# PHAS-AmpController.net
KiCad netlist of a schematic drawn in EAGLE
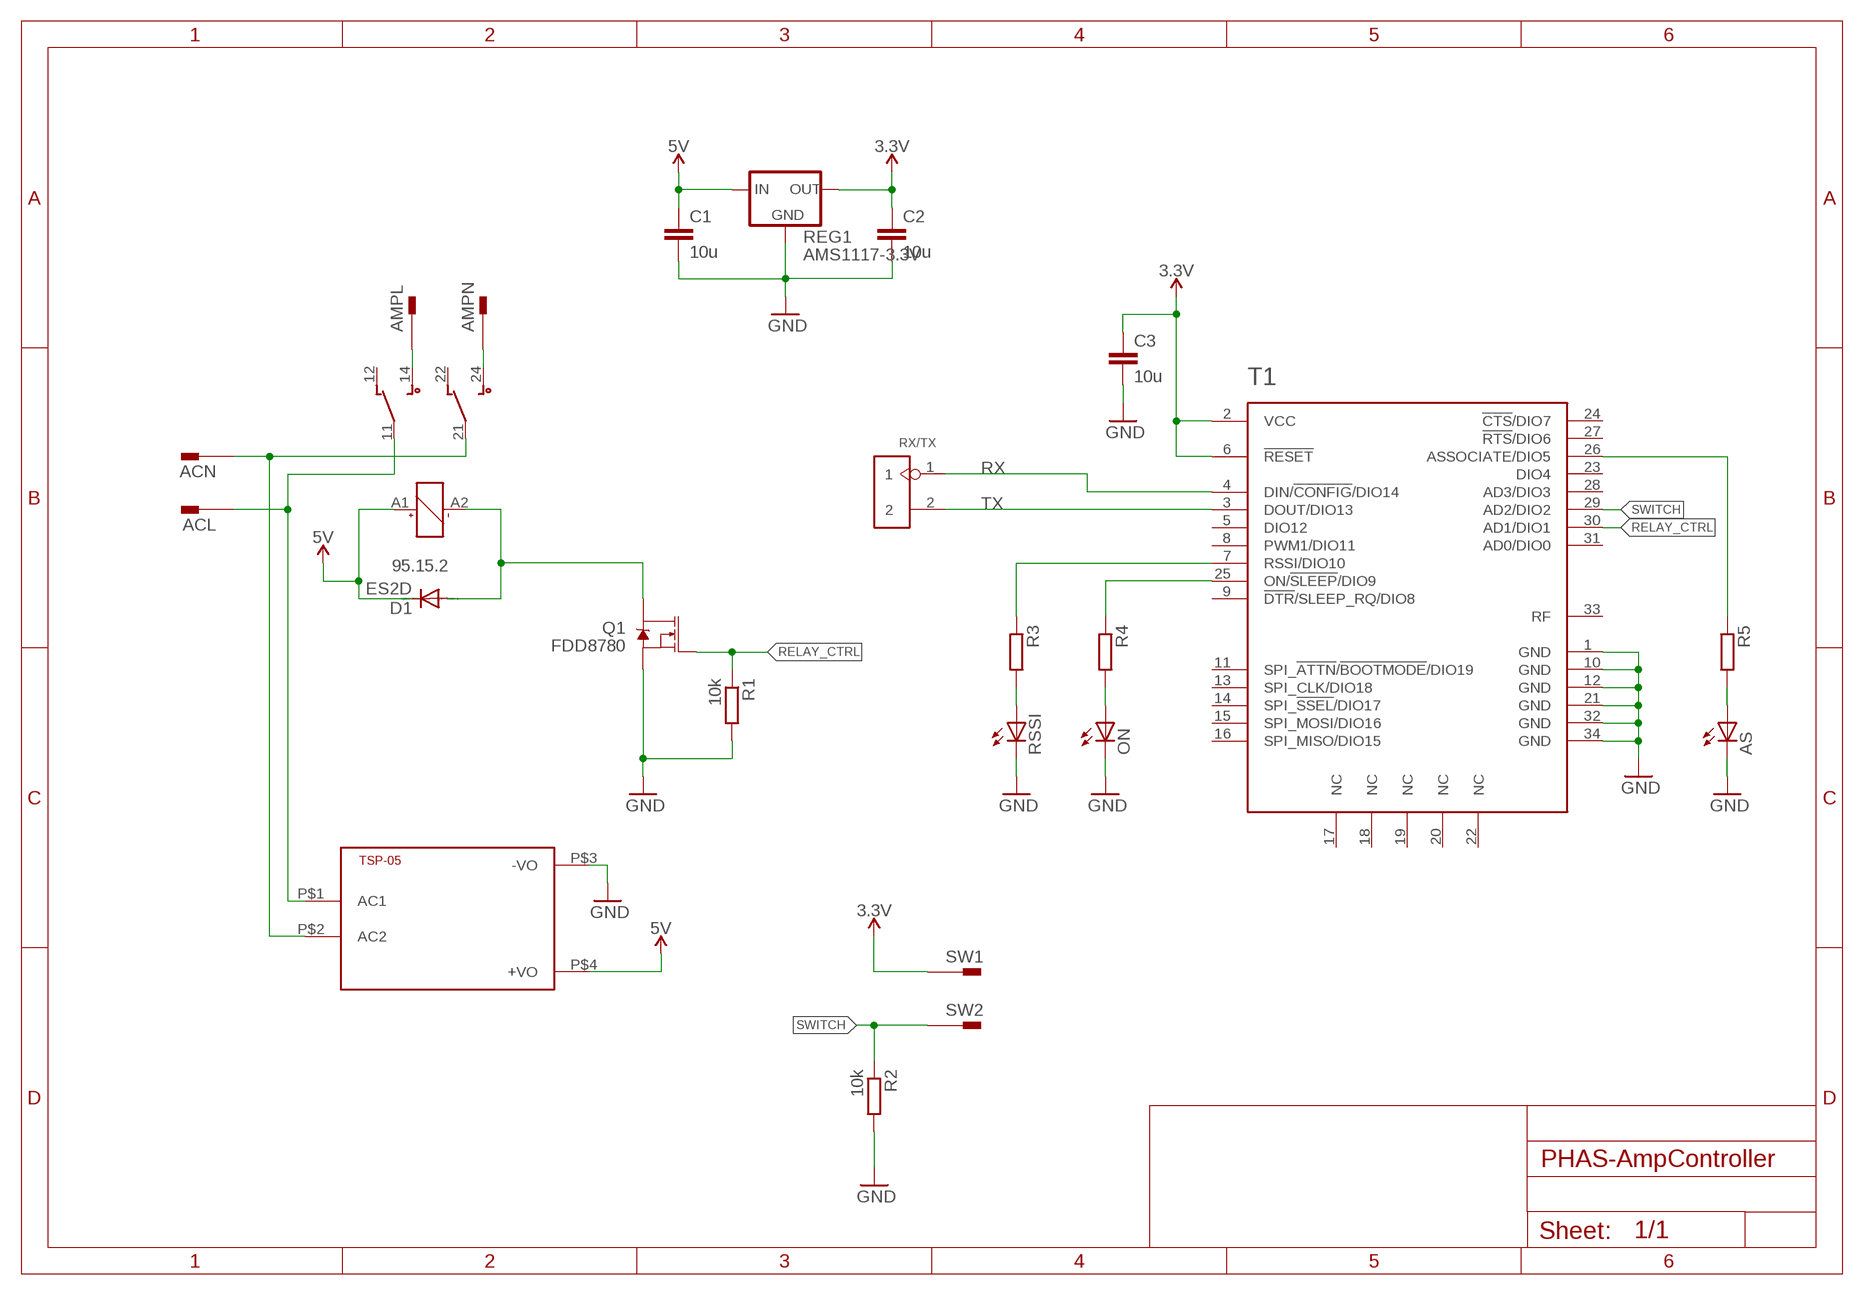
[diagram p0: schematic, sheet 1]

(export (version "E")
  (design (tool "Eeschema 10.0.6"))
  (components
    (comp (ref "ACL")
      (value "PIN2F061.100")
      (footprint "eagle-import:F061.100")
      (libsource (lib "eagle-import") (part "PIN2F061.100"))
    )
    (comp (ref "ACN")
      (value "PIN2F061.100")
      (footprint "eagle-import:F061.100")
      (libsource (lib "eagle-import") (part "PIN2F061.100"))
    )
    (comp (ref "AMPL")
      (value "PIN2F061.100")
      (footprint "eagle-import:F061.100")
      (libsource (lib "eagle-import") (part "PIN2F061.100"))
    )
    (comp (ref "AMPN")
      (value "PIN2F061.100")
      (footprint "eagle-import:F061.100")
      (libsource (lib "eagle-import") (part "PIN2F061.100"))
    )
    (comp (ref "AS")
      (value "LEDCHIPLED_0805")
      (footprint "eagle-import:CHIPLED_0805")
      (libsource (lib "eagle-import") (part "LEDCHIPLED_0805"))
    )
    (comp (ref "C1")
      (value "10u")
      (footprint "eagle-import:C0805")
      (libsource (lib "eagle-import") (part "C-EUC0805"))
    )
    (comp (ref "C2")
      (value "10u")
      (footprint "eagle-import:C0805")
      (libsource (lib "eagle-import") (part "C-EUC0805"))
    )
    (comp (ref "C3")
      (value "10u")
      (footprint "eagle-import:C0805")
      (libsource (lib "eagle-import") (part "C-EUC0805"))
    )
    (comp (ref "D1")
      (value "ES2D")
      (footprint "eagle-import:SMB")
      (libsource (lib "eagle-import") (part "ES2D"))
    )
    (comp (ref "ON")
      (value "LEDCHIPLED_0805")
      (footprint "eagle-import:CHIPLED_0805")
      (libsource (lib "eagle-import") (part "LEDCHIPLED_0805"))
    )
    (comp (ref "Q1")
      (value "FDD8780")
      (footprint "eagle-import:DPAK")
      (libsource (lib "eagle-import") (part "MOSFET-NCH-FDD8780"))
    )
    (comp (ref "R1")
      (value "10k")
      (footprint "eagle-import:R0805")
      (libsource (lib "eagle-import") (part "R-EU_R0805"))
    )
    (comp (ref "R2")
      (value "10k")
      (footprint "eagle-import:R0805")
      (libsource (lib "eagle-import") (part "R-EU_R0805"))
    )
    (comp (ref "R3")
      (value "R-EU_R0805")
      (footprint "eagle-import:R0805")
      (libsource (lib "eagle-import") (part "R-EU_R0805"))
    )
    (comp (ref "R4")
      (value "R-EU_R0805")
      (footprint "eagle-import:R0805")
      (libsource (lib "eagle-import") (part "R-EU_R0805"))
    )
    (comp (ref "R5")
      (value "R-EU_R0805")
      (footprint "eagle-import:R0805")
      (libsource (lib "eagle-import") (part "R-EU_R0805"))
    )
    (comp (ref "REG1")
      (value "AMS1117-3.3V")
      (footprint "eagle-import:SOT223")
      (fields (field (name "MF") "Texas Instruments") (field (name "MPN") "LM1117MP-3.3"))
      (libsource (lib "eagle-import") (part "LM1117?-MP3.3"))
    )
    (comp (ref "RL1")
      (value "95.15.2")
      (footprint "eagle-import:95.15.2")
      (libsource (lib "eagle-import") (part "95.15.2"))
    )
    (comp (ref "RSSI")
      (value "LEDCHIPLED_0805")
      (footprint "eagle-import:CHIPLED_0805")
      (libsource (lib "eagle-import") (part "LEDCHIPLED_0805"))
    )
    (comp (ref "RX/TX")
      (value "DIP-BLACK-MALE-HEADER-VERT(2P-2.54)")
      (footprint "eagle-import:H2-2.54")
      (fields (field (name "MPN") "P125-1102A0BS116A1"))
      (libsource (lib "eagle-import") (part "DIP-BLACK-MALE-HEADER-VERT(2P-2.54)"))
    )
    (comp (ref "SW1")
      (value "PIN2F061.100")
      (footprint "eagle-import:F061.100")
      (libsource (lib "eagle-import") (part "PIN2F061.100"))
    )
    (comp (ref "SW2")
      (value "PIN2F061.100")
      (footprint "eagle-import:F061.100")
      (libsource (lib "eagle-import") (part "PIN2F061.100"))
    )
    (comp (ref "T1")
      (value "XBEE3-MICRO")
      (footprint "eagle-import:XBEE3-MICRO")
      (libsource (lib "eagle-import") (part "XBEE3-MICRO"))
    )
    (comp (ref "TSP-05")
      (value "HKLPM01")
      (footprint "eagle-import:HKLPM01")
      (libsource (lib "eagle-import") (part "HKLPM01"))
    )
  )
  (nets
    (net (code "1") (name "/RX") (class "Default")
      (node (ref "RX/TX") (pin "1") (pinfunction "1_1") (pintype "bidirectional"))
      (node (ref "T1") (pin "4") (pinfunction "DIN/~{CONFIG}/DIO14_4") (pintype "bidirectional"))
    )
    (net (code "2") (name "/TX") (class "Default")
      (node (ref "RX/TX") (pin "2") (pinfunction "2_2") (pintype "bidirectional"))
      (node (ref "T1") (pin "3") (pinfunction "DOUT/DIO13_3") (pintype "bidirectional"))
    )
    (net (code "3") (name "3.3V") (class "Default")
      (node (ref "C2") (pin "1") (pinfunction "1_1") (pintype "passive"))
      (node (ref "C3") (pin "1") (pinfunction "1_1") (pintype "passive"))
      (node (ref "REG1") (pin "2") (pinfunction "OUT_2") (pintype "passive"))
      (node (ref "REG1") (pin "4") (pinfunction "OUT_4") (pintype "passive"))
      (node (ref "SW1") (pin "A1") (pinfunction "1_A1") (pintype "passive"))
      (node (ref "SW1") (pin "A2") (pinfunction "1_A2") (pintype "passive"))
      (node (ref "T1") (pin "2") (pinfunction "VCC_2") (pintype "power_in"))
      (node (ref "T1") (pin "6") (pinfunction "~{RESET}_6") (pintype "input"))
    )
    (net (code "4") (name "5V") (class "Default")
      (node (ref "C1") (pin "1") (pinfunction "1_1") (pintype "passive"))
      (node (ref "D1") (pin "C") (pinfunction "C_C") (pintype "passive"))
      (node (ref "REG1") (pin "3") (pinfunction "IN_3") (pintype "input"))
      (node (ref "RL1") (pin "A1") (pinfunction "A1_A1") (pintype "passive"))
      (node (ref "TSP-05") (pin "P$4") (pinfunction "+VO_P$4") (pintype "bidirectional"))
    )
    (net (code "5") (name "GND") (class "Default")
      (node (ref "AS") (pin "C") (pinfunction "C_C") (pintype "passive"))
      (node (ref "C1") (pin "2") (pinfunction "2_2") (pintype "passive"))
      (node (ref "C2") (pin "2") (pinfunction "2_2") (pintype "passive"))
      (node (ref "C3") (pin "2") (pinfunction "2_2") (pintype "passive"))
      (node (ref "ON") (pin "C") (pinfunction "C_C") (pintype "passive"))
      (node (ref "Q1") (pin "3") (pinfunction "S_3") (pintype "bidirectional"))
      (node (ref "R1") (pin "2") (pinfunction "2_2") (pintype "passive"))
      (node (ref "R2") (pin "2") (pinfunction "2_2") (pintype "passive"))
      (node (ref "REG1") (pin "1") (pinfunction "GND_1") (pintype "input"))
      (node (ref "RSSI") (pin "C") (pinfunction "C_C") (pintype "passive"))
      (node (ref "T1") (pin "1") (pinfunction "GND_1") (pintype "power_in"))
      (node (ref "T1") (pin "10") (pinfunction "GND_10") (pintype "power_in"))
      (node (ref "T1") (pin "12") (pinfunction "GND_12") (pintype "power_in"))
      (node (ref "T1") (pin "21") (pinfunction "GND_21") (pintype "power_in"))
      (node (ref "T1") (pin "32") (pinfunction "GND_32") (pintype "power_in"))
      (node (ref "T1") (pin "34") (pinfunction "GND_34") (pintype "power_in"))
      (node (ref "TSP-05") (pin "P$3") (pinfunction "-VO_P$3") (pintype "bidirectional"))
    )
    (net (code "6") (name "Net-(AMPL-1-PadA1)") (class "Default")
      (node (ref "AMPL") (pin "A1") (pinfunction "1_A1") (pintype "passive"))
      (node (ref "AMPL") (pin "A2") (pinfunction "1_A2") (pintype "passive"))
      (node (ref "RL1") (pin "14") (pinfunction "14_14") (pintype "passive"))
    )
    (net (code "7") (name "Net-(AMPN-1-PadA1)") (class "Default")
      (node (ref "AMPN") (pin "A1") (pinfunction "1_A1") (pintype "passive"))
      (node (ref "AMPN") (pin "A2") (pinfunction "1_A2") (pintype "passive"))
      (node (ref "RL1") (pin "24") (pinfunction "24_24") (pintype "passive"))
    )
    (net (code "8") (name "Net-(AS-PadA)") (class "Default")
      (node (ref "AS") (pin "A") (pinfunction "A_A") (pintype "passive"))
      (node (ref "R5") (pin "2") (pinfunction "2_2") (pintype "passive"))
    )
    (net (code "9") (name "Net-(ON-PadA)") (class "Default")
      (node (ref "ON") (pin "A") (pinfunction "A_A") (pintype "passive"))
      (node (ref "R4") (pin "2") (pinfunction "2_2") (pintype "passive"))
    )
    (net (code "10") (name "Net-(Q1-D)") (class "Default")
      (node (ref "D1") (pin "A") (pinfunction "A_A") (pintype "passive"))
      (node (ref "Q1") (pin "4") (pinfunction "D_4") (pintype "bidirectional"))
      (node (ref "RL1") (pin "A2") (pinfunction "A2_A2") (pintype "passive"))
    )
    (net (code "11") (name "Net-(R3-Pad2)") (class "Default")
      (node (ref "R3") (pin "2") (pinfunction "2_2") (pintype "passive"))
      (node (ref "RSSI") (pin "A") (pinfunction "A_A") (pintype "passive"))
    )
    (net (code "12") (name "Net-(T1-ASSOCIATE{slash}DIO5)") (class "Default")
      (node (ref "R5") (pin "1") (pinfunction "1_1") (pintype "passive"))
      (node (ref "T1") (pin "26") (pinfunction "ASSOCIATE/DIO5_26") (pintype "bidirectional"))
    )
    (net (code "13") (name "Net-(T1-ON{slash}~{SLEEP}{slash}DIO9)") (class "Default")
      (node (ref "R4") (pin "1") (pinfunction "1_1") (pintype "passive"))
      (node (ref "T1") (pin "25") (pinfunction "ON/~{SLEEP}/DIO9_25") (pintype "bidirectional"))
    )
    (net (code "14") (name "Net-(T1-RSSI{slash}DIO10)") (class "Default")
      (node (ref "R3") (pin "1") (pinfunction "1_1") (pintype "passive"))
      (node (ref "T1") (pin "7") (pinfunction "RSSI/DIO10_7") (pintype "bidirectional"))
    )
    (net (code "15") (name "Net-(TSP-05-AC1)") (class "Default")
      (node (ref "ACL") (pin "A1") (pinfunction "1_A1") (pintype "passive"))
      (node (ref "ACL") (pin "A2") (pinfunction "1_A2") (pintype "passive"))
      (node (ref "RL1") (pin "11") (pinfunction "11_11") (pintype "passive"))
      (node (ref "TSP-05") (pin "P$1") (pinfunction "AC1_P$1") (pintype "bidirectional"))
    )
    (net (code "16") (name "Net-(TSP-05-AC2)") (class "Default")
      (node (ref "ACN") (pin "A1") (pinfunction "1_A1") (pintype "passive"))
      (node (ref "ACN") (pin "A2") (pinfunction "1_A2") (pintype "passive"))
      (node (ref "RL1") (pin "21") (pinfunction "21_21") (pintype "passive"))
      (node (ref "TSP-05") (pin "P$2") (pinfunction "AC2_P$2") (pintype "bidirectional"))
    )
    (net (code "17") (name "RELAY_CTRL") (class "Default")
      (node (ref "Q1") (pin "1") (pinfunction "G_1") (pintype "bidirectional"))
      (node (ref "R1") (pin "1") (pinfunction "1_1") (pintype "passive"))
      (node (ref "T1") (pin "30") (pinfunction "AD1/DIO1_30") (pintype "bidirectional"))
    )
    (net (code "18") (name "SWITCH") (class "Default")
      (node (ref "R2") (pin "1") (pinfunction "1_1") (pintype "passive"))
      (node (ref "SW2") (pin "A1") (pinfunction "1_A1") (pintype "passive"))
      (node (ref "SW2") (pin "A2") (pinfunction "1_A2") (pintype "passive"))
      (node (ref "T1") (pin "29") (pinfunction "AD2/DIO2_29") (pintype "bidirectional"))
    )
    (net (code "19") (name "unconnected-(RL1-Pad12)") (class "Default")
      (node (ref "RL1") (pin "12") (pinfunction "12_12") (pintype "passive"))
    )
    (net (code "20") (name "unconnected-(RL1-Pad22)") (class "Default")
      (node (ref "RL1") (pin "22") (pinfunction "22_22") (pintype "passive"))
    )
    (net (code "21") (name "unconnected-(T1-AD0{slash}DIO0-Pad31)") (class "Default")
      (node (ref "T1") (pin "31") (pinfunction "AD0/DIO0_31") (pintype "bidirectional"))
    )
    (net (code "22") (name "unconnected-(T1-AD3{slash}DIO3-Pad28)") (class "Default")
      (node (ref "T1") (pin "28") (pinfunction "AD3/DIO3_28") (pintype "bidirectional"))
    )
    (net (code "23") (name "unconnected-(T1-DIO4-Pad23)") (class "Default")
      (node (ref "T1") (pin "23") (pinfunction "DIO4_23") (pintype "bidirectional"))
    )
    (net (code "24") (name "unconnected-(T1-DIO12-Pad5)") (class "Default")
      (node (ref "T1") (pin "5") (pinfunction "DIO12_5") (pintype "bidirectional"))
    )
    (net (code "25") (name "unconnected-(T1-NC-Pad17)") (class "Default")
      (node (ref "T1") (pin "17") (pinfunction "NC_17") (pintype "bidirectional"))
    )
    (net (code "26") (name "unconnected-(T1-NC-Pad18)") (class "Default")
      (node (ref "T1") (pin "18") (pinfunction "NC_18") (pintype "bidirectional"))
    )
    (net (code "27") (name "unconnected-(T1-NC-Pad19)") (class "Default")
      (node (ref "T1") (pin "19") (pinfunction "NC_19") (pintype "bidirectional"))
    )
    (net (code "28") (name "unconnected-(T1-NC-Pad20)") (class "Default")
      (node (ref "T1") (pin "20") (pinfunction "NC_20") (pintype "bidirectional"))
    )
    (net (code "29") (name "unconnected-(T1-NC-Pad22)") (class "Default")
      (node (ref "T1") (pin "22") (pinfunction "NC_22") (pintype "bidirectional"))
    )
    (net (code "30") (name "unconnected-(T1-PWM1{slash}DIO11-Pad8)") (class "Default")
      (node (ref "T1") (pin "8") (pinfunction "PWM1/DIO11_8") (pintype "bidirectional"))
    )
    (net (code "31") (name "unconnected-(T1-RF-Pad33)") (class "Default")
      (node (ref "T1") (pin "33") (pinfunction "RF_33") (pintype "output"))
    )
    (net (code "32") (name "unconnected-(T1-SPI_CLK{slash}DIO18-Pad13)") (class "Default")
      (node (ref "T1") (pin "13") (pinfunction "SPI_CLK/DIO18_13") (pintype "bidirectional"))
    )
    (net (code "33") (name "unconnected-(T1-SPI_MISO{slash}DIO15-Pad16)") (class "Default")
      (node (ref "T1") (pin "16") (pinfunction "SPI_MISO/DIO15_16") (pintype "bidirectional"))
    )
    (net (code "34") (name "unconnected-(T1-SPI_MOSI{slash}DIO16-Pad15)") (class "Default")
      (node (ref "T1") (pin "15") (pinfunction "SPI_MOSI/DIO16_15") (pintype "bidirectional"))
    )
    (net (code "35") (name "unconnected-(T1-SPI_~{ATTN}{slash}~{BOOTMODE}{slash}DIO19-Pad11)") (class "Default")
      (node (ref "T1") (pin "11") (pinfunction "SPI_~{ATTN}/~{BOOTMODE}/DIO19_11") (pintype "bidirectional"))
    )
    (net (code "36") (name "unconnected-(T1-SPI_~{SSEL}{slash}DIO17-Pad14)") (class "Default")
      (node (ref "T1") (pin "14") (pinfunction "SPI_~{SSEL}/DIO17_14") (pintype "bidirectional"))
    )
    (net (code "37") (name "unconnected-(T1-~{CTS}{slash}DIO7-Pad24)") (class "Default")
      (node (ref "T1") (pin "24") (pinfunction "~{CTS}/DIO7_24") (pintype "bidirectional"))
    )
    (net (code "38") (name "unconnected-(T1-~{DTR}{slash}SLEEP_RQ{slash}DIO8-Pad9)") (class "Default")
      (node (ref "T1") (pin "9") (pinfunction "~{DTR}/SLEEP_RQ/DIO8_9") (pintype "bidirectional"))
    )
    (net (code "39") (name "unconnected-(T1-~{RTS}{slash}DIO6-Pad27)") (class "Default")
      (node (ref "T1") (pin "27") (pinfunction "~{RTS}/DIO6_27") (pintype "bidirectional"))
    )
  )
)
